# M_PWR.net
KiCad netlist of a schematic drawn in Altium Designer
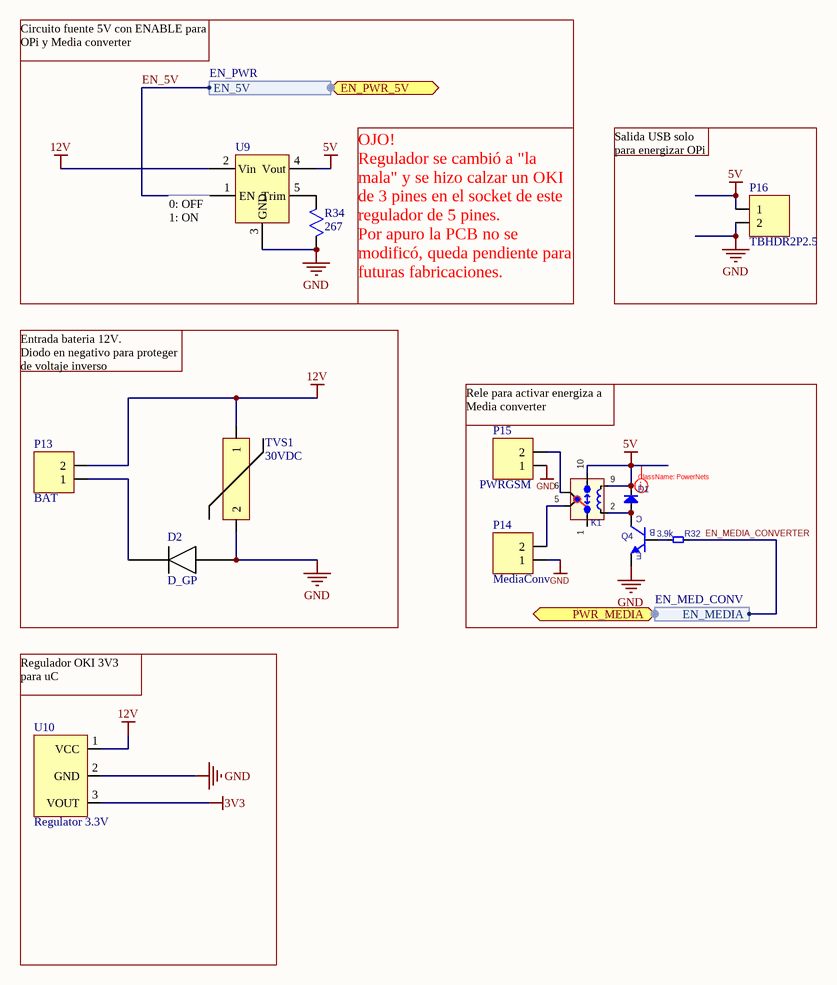
[diagram p0: M_PWR.SchDoc]

(export (version "E")
  (design (tool "Eeschema 10.0.6"))
  (components
    (comp (ref "D1")
      (value "DIODE_EIL")
      (footprint "DIOD_SOD123 - REFLOW")
      (description "DIODE GEN PURP 100V 150MA SOD123")
      (fields (field (name "PARTNO") "1N4148W-TP") (field (name "DIGI-KEY PART NUMBER") "1N4148WTPMSCT-ND"))
      (libsource (lib "0_LibAltiumEsquematicosEIL") (part "DIODE_EIL"))
    )
    (comp (ref "D2")
      (value "D_GP")
      (footprint "SMA")
      (description "Single Diode Rectifier SMD")
      (fields (field (name "DIGI-KEY PART NUMBER") "641-1707-1-ND") (field (name "PARTNO") "CDBA540-HF"))
      (libsource (lib "PAT_Library") (part "D_GP"))
    )
    (comp (ref "K1")
      (value "RELAY_METALTEX_MB1RC-5V_SPDT_EIL")
      (footprint "RELAY_METALTEX_MB1RC-5V_SPDT THR")
      (description "RELAY GENERAL PURPOSE SPDT 1A 5V")
      (fields (field (name "PARTNO") "G5V-1-DC5") (field (name "DIGI-KEY PART NUMBER") "255-1092-ND"))
      (libsource (lib "0_LibAltiumEsquematicosEIL") (part "RELAY_METALTEX_MB1RC-5V_SPDT_EIL"))
    )
    (comp (ref "P13")
      (value "BAT")
      (footprint "TBHDR2P3.5VERTICAL")
      (description "Connector 2 positions with pitch 3.5mm")
      (fields (field (name "DIGI-KEY PART NUMBER") "732-2763-ND") (field (name "PARTNO") "691321100002"))
      (libsource (lib "PAT Connectors Board") (part "TBHDR2P3.5"))
    )
    (comp (ref "P14")
      (value "MediaConv")
      (footprint "TBHDR2P3.5VERTICAL")
      (description "Connector 2 positions with pitch 3.5mm")
      (fields (field (name "DIGI-KEY PART NUMBER") "732-2763-ND") (field (name "PARTNO") "691321100002"))
      (libsource (lib "PAT Connectors Board") (part "TBHDR2P3.5"))
    )
    (comp (ref "P15")
      (value "PWRGSM")
      (footprint "TBHDR2P3.5VERTICAL")
      (description "Connector 2 positions with pitch 3.5mm")
      (fields (field (name "DIGI-KEY PART NUMBER") "732-2763-ND") (field (name "PARTNO") "691321100002"))
      (libsource (lib "PAT Connectors Board") (part "TBHDR2P3.5"))
    )
    (comp (ref "P16")
      (value "TBHDR2P2.5")
      (footprint "TBR2.5")
      (description "Connector 2 positions with pitch 3.5mm")
      (fields
        (field (name "DIGI-KEY PART NUMBER") "277-2308-1-ND")
        (field (name "MANUFACTURERS PART NUMBER") "1778625")
      )
      (libsource (lib "") (part "TBHDR2P3.5_1"))
    )
    (comp (ref "Q4")
      (value "TRAN_BJT_NPN_EIL")
      (footprint "3PIN_SOT-23 BJT - REFLOW")
      (description "TRANS NPN 45V 0.5A SOT23")
      (fields
        (field (name "PARTNO") "BC817-40LT1G")
        (field (name "DIGI-KEY PART NUMBER") "BC817-40LT1GOSCT-ND")
      )
      (libsource (lib "0_LibAltiumEsquematicosEIL") (part "TRAN_BJT_NPN_EIL"))
    )
    (comp (ref "R32")
      (value "3.9k")
      (footprint "PASS_RESC0603 - REFLOW")
      (description "RES SMD 3.9K OHM 1% 1/10W 0603")
      (fields
        (field (name "PARTNO") "RC0603FR-073K9L")
        (field (name "DIGI-KEY PART NUMBER") "311-3.90KHRCT-ND")
      )
      (libsource (lib "0_LibAltiumEsquematicosEIL") (part "PASS_R_EIL"))
    )
    (comp (ref "R34")
      (value "267")
      (footprint "ResistorSMD0805")
      (description "Chip Resistor SMD")
      (fields
        (field (name "DIGI-KEY PART NUMBER") "P20215CT-ND")
        (field (name "MANUFACTURERS PART NUMBER") "ERJ-PB3D2670V")
      )
      (libsource (lib "PAT_Library") (part "ResistorSMD"))
    )
    (comp (ref "TVS1")
      (value "30VDC")
      (footprint "Varistor")
      (description "Varistor SMD")
      (fields
        (field (name "DIGI-KEY PART NUMBER") "P7347CT-ND")
        (field (name "MANUFACTURERS PART NUMBER") "ERZ-VF2M330")
      )
      (libsource (lib "PAT_Library") (part "Varistor"))
    )
    (comp (ref "U9")
      (value "DCDC 5V/3A")
      (footprint "OKR")
      (description "Non-Isolated PoL Module DC DC Converter 1 Output 0.59 ~ 6 V 3A 4.5V - 14V Input")
      (fields (field (name "DIGI-KEY PART NUMBER") "811-2115-5-ND") (field (name "PARTNO") "OKR-T/3-W12-C"))
      (libsource (lib "PAT_Library") (part "DCDC 5V/3A"))
    )
    (comp (ref "U10")
      (value "Regulator 3.3V")
      (footprint "OKI78SR")
      (description "Regulator DC-DC 3.3V 1.5A")
      (fields
        (field (name "DIGI-KEY PART NUMBER") "811-2195-5-ND")
        (field (name "PARTNO") "OKI-78SR-3.3/1.5-W36-C")
      )
      (libsource (lib "PAT_Library") (part "OKI78SR"))
    )
  )
  (nets
    (net (code "3") (name "/EN_5V") (class "Default")
      (node (ref "U9") (pin "1") (pinfunction "EN_1") (pintype "passive"))
    )
    (net (code "4") (name "/EN_MEDIA_CONVERTER") (class "Default")
      (node (ref "R32") (pin "2") (pinfunction "2_2") (pintype "passive"))
    )
    (net (code "7") (name "3V3") (class "Default")
      (node (ref "U10") (pin "3") (pinfunction "VOUT_3") (pintype "passive"))
    )
    (net (code "8") (name "5V") (class "Default")
      (node (ref "D1") (pin "K") (pinfunction "K_K") (pintype "passive"))
      (node (ref "K1") (pin "10") (pinfunction "10_10") (pintype "passive"))
      (node (ref "K1") (pin "9") (pinfunction "9_9") (pintype "passive"))
      (node (ref "P16") (pin "1") (pinfunction "1_1") (pintype "passive"))
      (node (ref "U9") (pin "4") (pinfunction "Vout_4") (pintype "passive"))
    )
    (net (code "9") (name "12V") (class "Default")
      (node (ref "P13") (pin "2") (pinfunction "2_2") (pintype "passive"))
      (node (ref "TVS1") (pin "1") (pinfunction "1_1") (pintype "passive"))
      (node (ref "U10") (pin "1") (pinfunction "VCC_1") (pintype "passive"))
      (node (ref "U9") (pin "2") (pinfunction "Vin_2") (pintype "passive"))
    )
    (net (code "10") (name "GND") (class "Default")
      (node (ref "D2") (pin "2") (pinfunction "2_2") (pintype "passive"))
      (node (ref "P14") (pin "1") (pinfunction "1_1") (pintype "passive"))
      (node (ref "P15") (pin "1") (pinfunction "1_1") (pintype "passive"))
      (node (ref "P16") (pin "2") (pinfunction "2_2") (pintype "passive"))
      (node (ref "Q4") (pin "E") (pinfunction "E_E") (pintype "passive"))
      (node (ref "R34") (pin "2") (pinfunction "2_2") (pintype "passive"))
      (node (ref "TVS1") (pin "2") (pinfunction "2_2") (pintype "passive"))
      (node (ref "U10") (pin "2") (pinfunction "GND_2") (pintype "passive"))
      (node (ref "U9") (pin "3") (pinfunction "GND_3") (pintype "passive"))
    )
    (net (code "11") (name "Net-(D1-PadA)") (class "Default")
      (node (ref "D1") (pin "A") (pinfunction "A_A") (pintype "passive"))
      (node (ref "K1") (pin "2") (pinfunction "2_2") (pintype "passive"))
      (node (ref "Q4") (pin "C") (pinfunction "C_C") (pintype "passive"))
    )
    (net (code "12") (name "Net-(D2-Pad1)") (class "Default")
      (node (ref "D2") (pin "1") (pinfunction "1_1") (pintype "passive"))
      (node (ref "P13") (pin "1") (pinfunction "1_1") (pintype "passive"))
    )
    (net (code "13") (name "Net-(K1-Pad5)") (class "Default")
      (node (ref "K1") (pin "5") (pinfunction "5_5") (pintype "passive"))
      (node (ref "P14") (pin "2") (pinfunction "2_2") (pintype "passive"))
    )
    (net (code "14") (name "Net-(K1-Pad6)") (class "Default")
      (node (ref "K1") (pin "6") (pinfunction "6_6") (pintype "passive"))
      (node (ref "P15") (pin "2") (pinfunction "2_2") (pintype "passive"))
    )
    (net (code "15") (name "Net-(Q4-PadB)") (class "Default")
      (node (ref "Q4") (pin "B") (pinfunction "B_B") (pintype "passive"))
      (node (ref "R32") (pin "1") (pinfunction "1_1") (pintype "passive"))
    )
    (net (code "16") (name "Net-(U9-Trim)") (class "Default")
      (node (ref "R34") (pin "1") (pinfunction "1_1") (pintype "passive"))
      (node (ref "U9") (pin "5") (pinfunction "Trim_5") (pintype "passive"))
    )
    (net (code "17") (name "unconnected-(K1-Pad1)") (class "Default")
      (node (ref "K1") (pin "1") (pinfunction "1_1") (pintype "passive"))
    )
  )
)
